# rt_solder_simple_V1_2.net
KiCad netlist of a schematic drawn in EAGLE
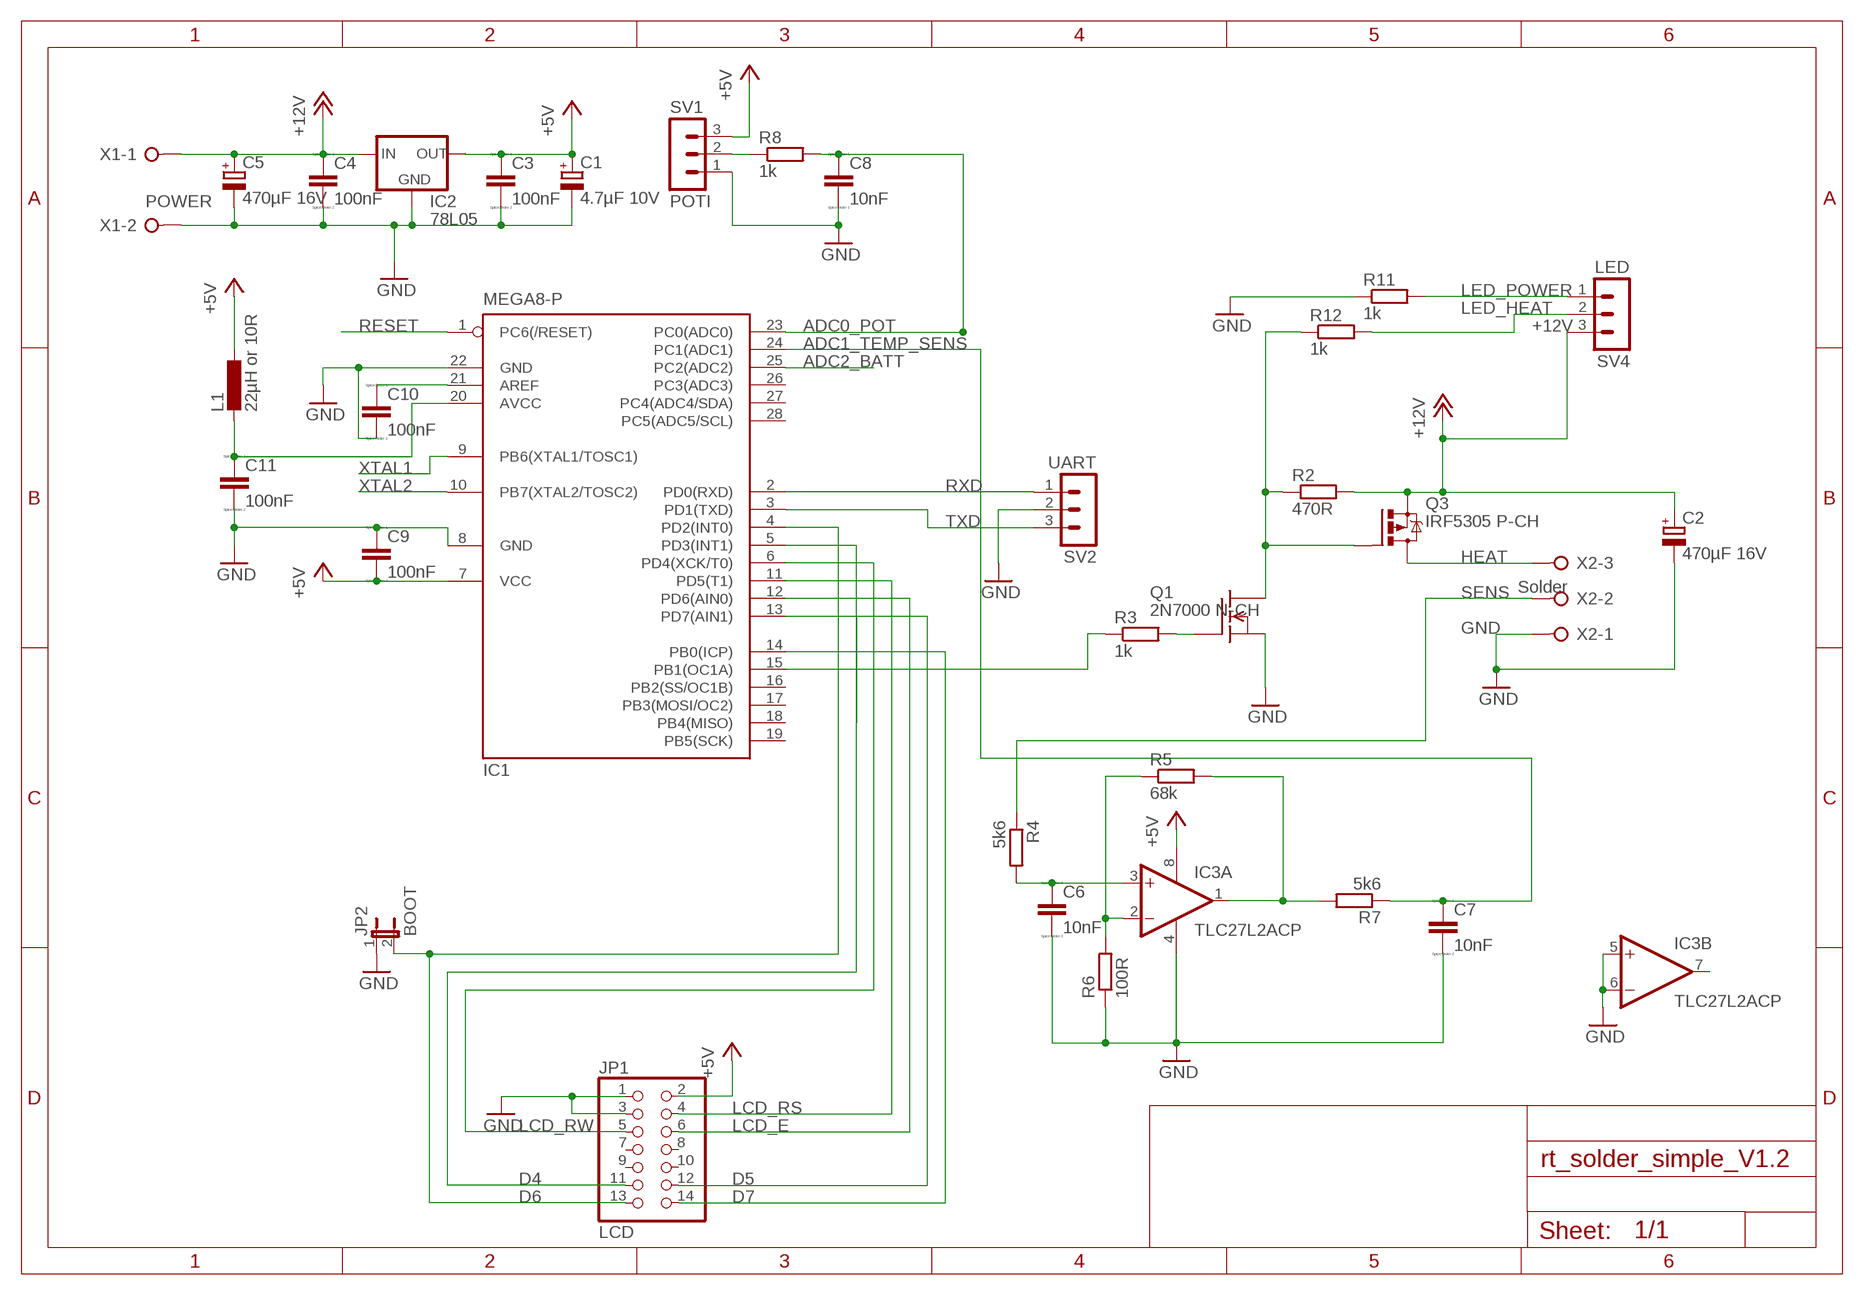
[diagram p0: schematic, sheet 1]

(export (version "E")
  (design (tool "Eeschema 10.0.6"))
  (components
    (comp (ref "C1")
      (value "4.7µF 10V")
      (footprint "eagle-import:E2,5-6")
      (libsource (lib "eagle-import") (part "CPOL-EUE2.5-6"))
    )
    (comp (ref "C2")
      (value "470µF 16V")
      (footprint "eagle-import:E3,5-10")
      (libsource (lib "eagle-import") (part "CPOL-EUE3.5-10"))
    )
    (comp (ref "C3")
      (value "100nF")
      (footprint "eagle-import:C050-035X075")
      (libsource (lib "eagle-import") (part "C-EU050-035X075"))
    )
    (comp (ref "C4")
      (value "100nF")
      (footprint "eagle-import:C050-035X075")
      (libsource (lib "eagle-import") (part "C-EU050-035X075"))
    )
    (comp (ref "C5")
      (value "470µF 16V")
      (footprint "eagle-import:E3,5-10")
      (libsource (lib "eagle-import") (part "CPOL-EUE3.5-10"))
    )
    (comp (ref "C6")
      (value "10nF")
      (footprint "eagle-import:C050-035X075")
      (libsource (lib "eagle-import") (part "C-EU050-035X075"))
    )
    (comp (ref "C7")
      (value "10nF")
      (footprint "eagle-import:C050-035X075")
      (libsource (lib "eagle-import") (part "C-EU050-035X075"))
    )
    (comp (ref "C8")
      (value "10nF")
      (footprint "eagle-import:C050-035X075")
      (libsource (lib "eagle-import") (part "C-EU050-035X075"))
    )
    (comp (ref "C9")
      (value "100nF")
      (footprint "eagle-import:C050-035X075")
      (libsource (lib "eagle-import") (part "C-EU050-035X075"))
    )
    (comp (ref "C10")
      (value "100nF")
      (footprint "eagle-import:C050-035X075")
      (libsource (lib "eagle-import") (part "C-EU050-035X075"))
    )
    (comp (ref "C11")
      (value "100nF")
      (footprint "eagle-import:C050-035X075")
      (libsource (lib "eagle-import") (part "C-EU050-035X075"))
    )
    (comp (ref "IC1")
      (value "MEGA8-P")
      (footprint "eagle-import:DIL28-3")
      (libsource (lib "eagle-import") (part "MEGA8-P"))
    )
    (comp (ref "IC2")
      (value "78L05")
      (footprint "eagle-import:78XXS")
      (libsource (lib "eagle-import") (part "78XXS"))
    )
    (comp (ref "IC3")
      (value "TLC27L2ACP")
      (footprint "eagle-import:DIL08")
      (libsource (lib "eagle-import") (part "TLC27LP2AC"))
    )
    (comp (ref "JP1")
      (value "LCD")
      (footprint "eagle-import:2X07")
      (libsource (lib "eagle-import") (part "PINHD-2X7"))
    )
    (comp (ref "JP2")
      (value "BOOT")
      (footprint "eagle-import:JP1")
      (libsource (lib "eagle-import") (part "JP1E"))
    )
    (comp (ref "L1")
      (value "22µH or 10R")
      (footprint "eagle-import:0207_10")
      (libsource (lib "eagle-import") (part "L-EU0207/10"))
    )
    (comp (ref "Q1")
      (value "2N7000 N-CH")
      (footprint "eagle-import:TO237")
      (libsource (lib "eagle-import") (part "VN2222KM"))
    )
    (comp (ref "Q3")
      (value "IRF5305 P-CH")
      (footprint "eagle-import:TO220BV")
      (libsource (lib "eagle-import") (part "IRF9530"))
    )
    (comp (ref "R2")
      (value "470R")
      (footprint "eagle-import:0207_10")
      (libsource (lib "eagle-import") (part "R-EU_0207/10"))
    )
    (comp (ref "R3")
      (value "1k")
      (footprint "eagle-import:0207_10")
      (libsource (lib "eagle-import") (part "R-EU_0207/10"))
    )
    (comp (ref "R4")
      (value "5k6")
      (footprint "eagle-import:0207_10")
      (libsource (lib "eagle-import") (part "R-EU_0207/10"))
    )
    (comp (ref "R5")
      (value "68k")
      (footprint "eagle-import:0207_10")
      (libsource (lib "eagle-import") (part "R-EU_0207/10"))
    )
    (comp (ref "R6")
      (value "100R")
      (footprint "eagle-import:0207_10")
      (libsource (lib "eagle-import") (part "R-EU_0207/10"))
    )
    (comp (ref "R7")
      (value "5k6")
      (footprint "eagle-import:0207_10")
      (libsource (lib "eagle-import") (part "R-EU_0207/10"))
    )
    (comp (ref "R8")
      (value "1k")
      (footprint "eagle-import:0207_10")
      (libsource (lib "eagle-import") (part "R-EU_0207/10"))
    )
    (comp (ref "R11")
      (value "1k")
      (footprint "eagle-import:0207_10")
      (libsource (lib "eagle-import") (part "R-EU_0207/10"))
    )
    (comp (ref "R12")
      (value "1k")
      (footprint "eagle-import:0207_10")
      (libsource (lib "eagle-import") (part "R-EU_0207/10"))
    )
    (comp (ref "SV1")
      (value "POTI")
      (footprint "eagle-import:MA03-1")
      (libsource (lib "eagle-import") (part "MA03-1"))
    )
    (comp (ref "SV2")
      (value "UART")
      (footprint "eagle-import:MA03-1")
      (libsource (lib "eagle-import") (part "MA03-1"))
    )
    (comp (ref "SV4")
      (value "LED")
      (footprint "eagle-import:MA03-1")
      (libsource (lib "eagle-import") (part "MA03-1"))
    )
    (comp (ref "X1")
      (value "POWER")
      (footprint "eagle-import:W237-132")
      (libsource (lib "eagle-import") (part "W237-02P"))
    )
    (comp (ref "X2")
      (value "Solder")
      (footprint "eagle-import:W237-3E")
      (libsource (lib "eagle-import") (part "W237-3E"))
    )
  )
  (nets
    (net (code "1") (name "+5V") (class "Default")
      (node (ref "C1") (pin "+") (pinfunction "+_+") (pintype "passive"))
      (node (ref "C3") (pin "1") (pinfunction "1_1") (pintype "passive"))
      (node (ref "C9") (pin "2") (pinfunction "2_2") (pintype "passive"))
      (node (ref "IC1") (pin "7") (pinfunction "VCC_7") (pintype "power_in"))
      (node (ref "IC2") (pin "OUT") (pinfunction "OUT_OUT") (pintype "passive"))
      (node (ref "IC3") (pin "8") (pinfunction "VDD_8") (pintype "power_in"))
      (node (ref "JP1") (pin "2") (pinfunction "2_2") (pintype "passive"))
      (node (ref "L1") (pin "1") (pinfunction "1_1") (pintype "passive"))
      (node (ref "SV1") (pin "3") (pinfunction "3_3") (pintype "passive"))
    )
    (net (code "2") (name "+12V") (class "Default")
      (node (ref "C2") (pin "+") (pinfunction "+_+") (pintype "passive"))
      (node (ref "C4") (pin "1") (pinfunction "1_1") (pintype "passive"))
      (node (ref "C5") (pin "+") (pinfunction "+_+") (pintype "passive"))
      (node (ref "IC2") (pin "IN") (pinfunction "IN_IN") (pintype "input"))
      (node (ref "Q3") (pin "S") (pinfunction "S_S") (pintype "passive"))
      (node (ref "R2") (pin "2") (pinfunction "2_2") (pintype "passive"))
      (node (ref "SV4") (pin "3") (pinfunction "3_3") (pintype "passive"))
      (node (ref "X1") (pin "1") (pinfunction "KL_1") (pintype "passive"))
    )
    (net (code "3") (name "/ADC0_POT") (class "Default")
      (node (ref "C8") (pin "1") (pinfunction "1_1") (pintype "passive"))
      (node (ref "IC1") (pin "23") (pinfunction "PC0(ADC0)_23") (pintype "bidirectional"))
      (node (ref "R8") (pin "2") (pinfunction "2_2") (pintype "passive"))
    )
    (net (code "4") (name "/ADC1_TEMP_SENS") (class "Default")
      (node (ref "C7") (pin "1") (pinfunction "1_1") (pintype "passive"))
      (node (ref "IC1") (pin "24") (pinfunction "PC1(ADC1)_24") (pintype "bidirectional"))
      (node (ref "R7") (pin "1") (pinfunction "1_1") (pintype "passive"))
    )
    (net (code "5") (name "/ADC2_BATT") (class "Default")
      (node (ref "IC1") (pin "25") (pinfunction "PC2(ADC2)_25") (pintype "bidirectional"))
    )
    (net (code "6") (name "/D4") (class "Default")
      (node (ref "IC1") (pin "5") (pinfunction "PD3(INT1)_5") (pintype "bidirectional"))
      (node (ref "JP1") (pin "11") (pinfunction "11_11") (pintype "passive"))
    )
    (net (code "7") (name "/D5") (class "Default")
      (node (ref "IC1") (pin "13") (pinfunction "PD7(AIN1)_13") (pintype "bidirectional"))
      (node (ref "JP1") (pin "12") (pinfunction "12_12") (pintype "passive"))
    )
    (net (code "8") (name "/D6") (class "Default")
      (node (ref "IC1") (pin "4") (pinfunction "PD2(INT0)_4") (pintype "bidirectional"))
      (node (ref "JP1") (pin "13") (pinfunction "13_13") (pintype "passive"))
      (node (ref "JP2") (pin "2") (pinfunction "2_2") (pintype "passive"))
    )
    (net (code "9") (name "/D7") (class "Default")
      (node (ref "IC1") (pin "14") (pinfunction "PB0(ICP)_14") (pintype "bidirectional"))
      (node (ref "JP1") (pin "14") (pinfunction "14_14") (pintype "passive"))
    )
    (net (code "10") (name "/HEAT") (class "Default")
      (node (ref "Q3") (pin "D") (pinfunction "D_D") (pintype "passive"))
      (node (ref "X2") (pin "3") (pinfunction "KL_3") (pintype "passive"))
    )
    (net (code "11") (name "/LCD_E") (class "Default")
      (node (ref "IC1") (pin "12") (pinfunction "PD6(AIN0)_12") (pintype "bidirectional"))
      (node (ref "JP1") (pin "6") (pinfunction "6_6") (pintype "passive"))
    )
    (net (code "12") (name "/LCD_RS") (class "Default")
      (node (ref "IC1") (pin "11") (pinfunction "PD5(T1)_11") (pintype "bidirectional"))
      (node (ref "JP1") (pin "4") (pinfunction "4_4") (pintype "passive"))
    )
    (net (code "13") (name "/LCD_RW") (class "Default")
      (node (ref "IC1") (pin "6") (pinfunction "PD4(XCK/T0)_6") (pintype "bidirectional"))
      (node (ref "JP1") (pin "5") (pinfunction "5_5") (pintype "passive"))
    )
    (net (code "14") (name "/LED_HEAT") (class "Default")
      (node (ref "R12") (pin "2") (pinfunction "2_2") (pintype "passive"))
      (node (ref "SV4") (pin "2") (pinfunction "2_2") (pintype "passive"))
    )
    (net (code "15") (name "/LED_POWER") (class "Default")
      (node (ref "R11") (pin "2") (pinfunction "2_2") (pintype "passive"))
      (node (ref "SV4") (pin "1") (pinfunction "1_1") (pintype "passive"))
    )
    (net (code "16") (name "/RESET") (class "Default")
      (node (ref "IC1") (pin "1") (pinfunction "PC6(/RESET)_1") (pintype "bidirectional"))
    )
    (net (code "17") (name "/RXD") (class "Default")
      (node (ref "IC1") (pin "2") (pinfunction "PD0(RXD)_2") (pintype "bidirectional"))
      (node (ref "SV2") (pin "1") (pinfunction "1_1") (pintype "passive"))
    )
    (net (code "18") (name "/SENS") (class "Default")
      (node (ref "R4") (pin "1") (pinfunction "1_1") (pintype "passive"))
      (node (ref "X2") (pin "2") (pinfunction "KL_2") (pintype "passive"))
    )
    (net (code "19") (name "/TXD") (class "Default")
      (node (ref "IC1") (pin "3") (pinfunction "PD1(TXD)_3") (pintype "bidirectional"))
      (node (ref "SV2") (pin "3") (pinfunction "3_3") (pintype "passive"))
    )
    (net (code "20") (name "/XTAL1") (class "Default")
      (node (ref "IC1") (pin "9") (pinfunction "PB6(XTAL1/TOSC1)_9") (pintype "bidirectional"))
    )
    (net (code "21") (name "/XTAL2") (class "Default")
      (node (ref "IC1") (pin "10") (pinfunction "PB7(XTAL2/TOSC2)_10") (pintype "bidirectional"))
    )
    (net (code "22") (name "GND") (class "Default")
      (node (ref "C1") (pin "-") (pinfunction "-_-") (pintype "passive"))
      (node (ref "C10") (pin "2") (pinfunction "2_2") (pintype "passive"))
      (node (ref "C11") (pin "2") (pinfunction "2_2") (pintype "passive"))
      (node (ref "C2") (pin "-") (pinfunction "-_-") (pintype "passive"))
      (node (ref "C3") (pin "2") (pinfunction "2_2") (pintype "passive"))
      (node (ref "C4") (pin "2") (pinfunction "2_2") (pintype "passive"))
      (node (ref "C5") (pin "-") (pinfunction "-_-") (pintype "passive"))
      (node (ref "C6") (pin "2") (pinfunction "2_2") (pintype "passive"))
      (node (ref "C7") (pin "2") (pinfunction "2_2") (pintype "passive"))
      (node (ref "C8") (pin "2") (pinfunction "2_2") (pintype "passive"))
      (node (ref "C9") (pin "1") (pinfunction "1_1") (pintype "passive"))
      (node (ref "IC1") (pin "22") (pinfunction "GND_22") (pintype "power_in"))
      (node (ref "IC1") (pin "8") (pinfunction "GND_8") (pintype "power_in"))
      (node (ref "IC2") (pin "GND") (pinfunction "GND_GND") (pintype "input"))
      (node (ref "IC3") (pin "4") (pinfunction "GND_4") (pintype "power_in"))
      (node (ref "IC3") (pin "5") (pinfunction "+IN_5") (pintype "input"))
      (node (ref "IC3") (pin "6") (pinfunction "-IN_6") (pintype "input"))
      (node (ref "JP1") (pin "1") (pinfunction "1_1") (pintype "passive"))
      (node (ref "JP1") (pin "3") (pinfunction "3_3") (pintype "passive"))
      (node (ref "JP2") (pin "1") (pinfunction "1_1") (pintype "passive"))
      (node (ref "Q1") (pin "3") (pinfunction "S_3") (pintype "passive"))
      (node (ref "R11") (pin "1") (pinfunction "1_1") (pintype "passive"))
      (node (ref "R6") (pin "1") (pinfunction "1_1") (pintype "passive"))
      (node (ref "SV1") (pin "1") (pinfunction "1_1") (pintype "passive"))
      (node (ref "SV2") (pin "2") (pinfunction "2_2") (pintype "passive"))
      (node (ref "X1") (pin "2") (pinfunction "KL_2") (pintype "passive"))
      (node (ref "X2") (pin "1") (pinfunction "KL_1") (pintype "passive"))
    )
    (net (code "23") (name "Net-(IC1-AREF)") (class "Default")
      (node (ref "C10") (pin "1") (pinfunction "1_1") (pintype "passive"))
      (node (ref "IC1") (pin "21") (pinfunction "AREF_21") (pintype "passive"))
    )
    (net (code "24") (name "Net-(IC1-AVCC)") (class "Default")
      (node (ref "C11") (pin "1") (pinfunction "1_1") (pintype "passive"))
      (node (ref "IC1") (pin "20") (pinfunction "AVCC_20") (pintype "power_in"))
      (node (ref "L1") (pin "2") (pinfunction "2_2") (pintype "passive"))
    )
    (net (code "25") (name "Net-(IC1-PB1(OC1A))") (class "Default")
      (node (ref "IC1") (pin "15") (pinfunction "PB1(OC1A)_15") (pintype "bidirectional"))
      (node (ref "R3") (pin "1") (pinfunction "1_1") (pintype "passive"))
    )
    (net (code "26") (name "Net-(IC3A-+IN)") (class "Default")
      (node (ref "C6") (pin "1") (pinfunction "1_1") (pintype "passive"))
      (node (ref "IC3") (pin "3") (pinfunction "+IN_3") (pintype "input"))
      (node (ref "R4") (pin "2") (pinfunction "2_2") (pintype "passive"))
    )
    (net (code "27") (name "Net-(IC3A--IN)") (class "Default")
      (node (ref "IC3") (pin "2") (pinfunction "-IN_2") (pintype "input"))
      (node (ref "R5") (pin "1") (pinfunction "1_1") (pintype "passive"))
      (node (ref "R6") (pin "2") (pinfunction "2_2") (pintype "passive"))
    )
    (net (code "28") (name "Net-(IC3A-OUT)") (class "Default")
      (node (ref "IC3") (pin "1") (pinfunction "OUT_1") (pintype "output"))
      (node (ref "R5") (pin "2") (pinfunction "2_2") (pintype "passive"))
      (node (ref "R7") (pin "2") (pinfunction "2_2") (pintype "passive"))
    )
    (net (code "29") (name "Net-(Q1-D)") (class "Default")
      (node (ref "Q1") (pin "1") (pinfunction "D_1") (pintype "passive"))
      (node (ref "Q3") (pin "G") (pinfunction "G_G") (pintype "passive"))
      (node (ref "R12") (pin "1") (pinfunction "1_1") (pintype "passive"))
      (node (ref "R2") (pin "1") (pinfunction "1_1") (pintype "passive"))
    )
    (net (code "30") (name "Net-(Q1-G)") (class "Default")
      (node (ref "Q1") (pin "2") (pinfunction "G_2") (pintype "passive"))
      (node (ref "R3") (pin "2") (pinfunction "2_2") (pintype "passive"))
    )
    (net (code "31") (name "Net-(R8-Pad1)") (class "Default")
      (node (ref "R8") (pin "1") (pinfunction "1_1") (pintype "passive"))
      (node (ref "SV1") (pin "2") (pinfunction "2_2") (pintype "passive"))
    )
    (net (code "32") (name "unconnected-(IC1-PB2(SS{slash}OC1B)-Pad16)") (class "Default")
      (node (ref "IC1") (pin "16") (pinfunction "PB2(SS/OC1B)_16") (pintype "bidirectional"))
    )
    (net (code "33") (name "unconnected-(IC1-PB3(MOSI{slash}OC2)-Pad17)") (class "Default")
      (node (ref "IC1") (pin "17") (pinfunction "PB3(MOSI/OC2)_17") (pintype "bidirectional"))
    )
    (net (code "34") (name "unconnected-(IC1-PB4(MISO)-Pad18)") (class "Default")
      (node (ref "IC1") (pin "18") (pinfunction "PB4(MISO)_18") (pintype "bidirectional"))
    )
    (net (code "35") (name "unconnected-(IC1-PB5(SCK)-Pad19)") (class "Default")
      (node (ref "IC1") (pin "19") (pinfunction "PB5(SCK)_19") (pintype "bidirectional"))
    )
    (net (code "36") (name "unconnected-(IC1-PC3(ADC3)-Pad26)") (class "Default")
      (node (ref "IC1") (pin "26") (pinfunction "PC3(ADC3)_26") (pintype "bidirectional"))
    )
    (net (code "37") (name "unconnected-(IC1-PC4(ADC4{slash}SDA)-Pad27)") (class "Default")
      (node (ref "IC1") (pin "27") (pinfunction "PC4(ADC4/SDA)_27") (pintype "bidirectional"))
    )
    (net (code "38") (name "unconnected-(IC1-PC5(ADC5{slash}SCL)-Pad28)") (class "Default")
      (node (ref "IC1") (pin "28") (pinfunction "PC5(ADC5/SCL)_28") (pintype "bidirectional"))
    )
    (net (code "39") (name "unconnected-(IC3B-OUT-Pad7)") (class "Default")
      (node (ref "IC3") (pin "7") (pinfunction "OUT_7") (pintype "output"))
    )
    (net (code "40") (name "unconnected-(JP1-Pad7)") (class "Default")
      (node (ref "JP1") (pin "7") (pinfunction "7_7") (pintype "passive"))
    )
    (net (code "41") (name "unconnected-(JP1-Pad8)") (class "Default")
      (node (ref "JP1") (pin "8") (pinfunction "8_8") (pintype "passive"))
    )
    (net (code "42") (name "unconnected-(JP1-Pad9)") (class "Default")
      (node (ref "JP1") (pin "9") (pinfunction "9_9") (pintype "passive"))
    )
    (net (code "43") (name "unconnected-(JP1-Pad10)") (class "Default")
      (node (ref "JP1") (pin "10") (pinfunction "10_10") (pintype "passive"))
    )
  )
)
